# mbot_node.net
KiCad netlist of a schematic drawn in EasyEDA Pro
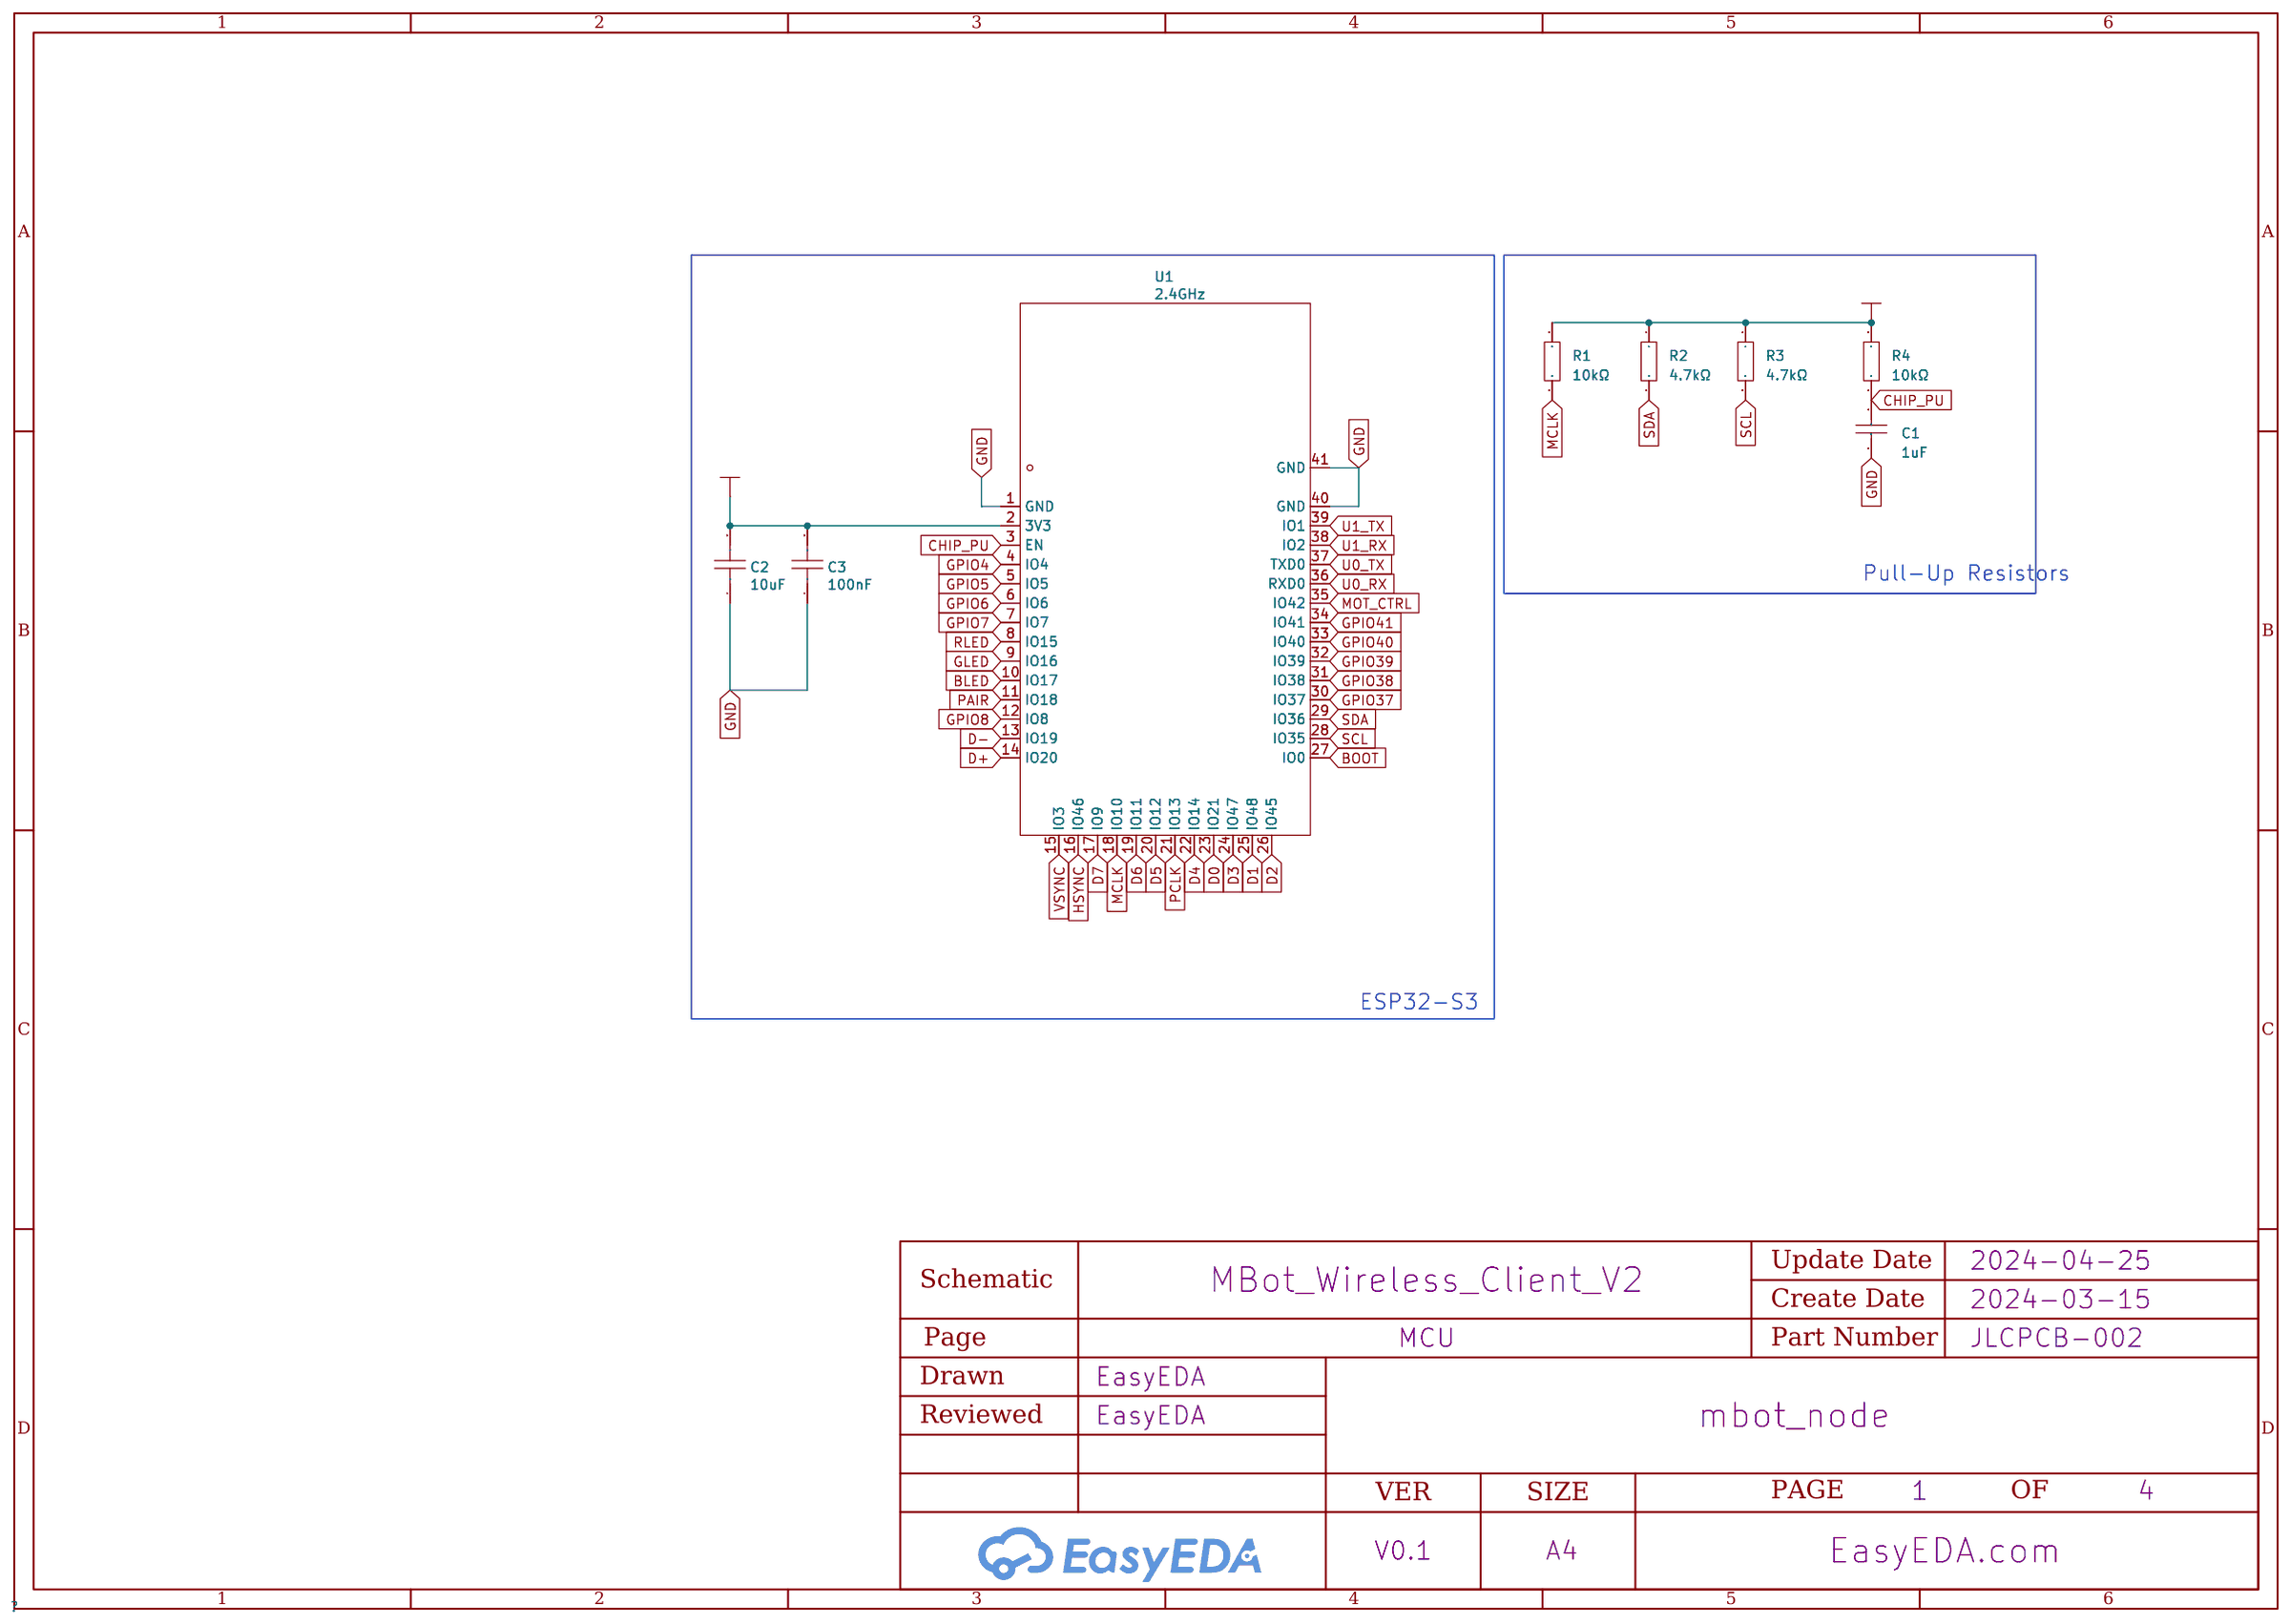
[diagram p0: MCU]
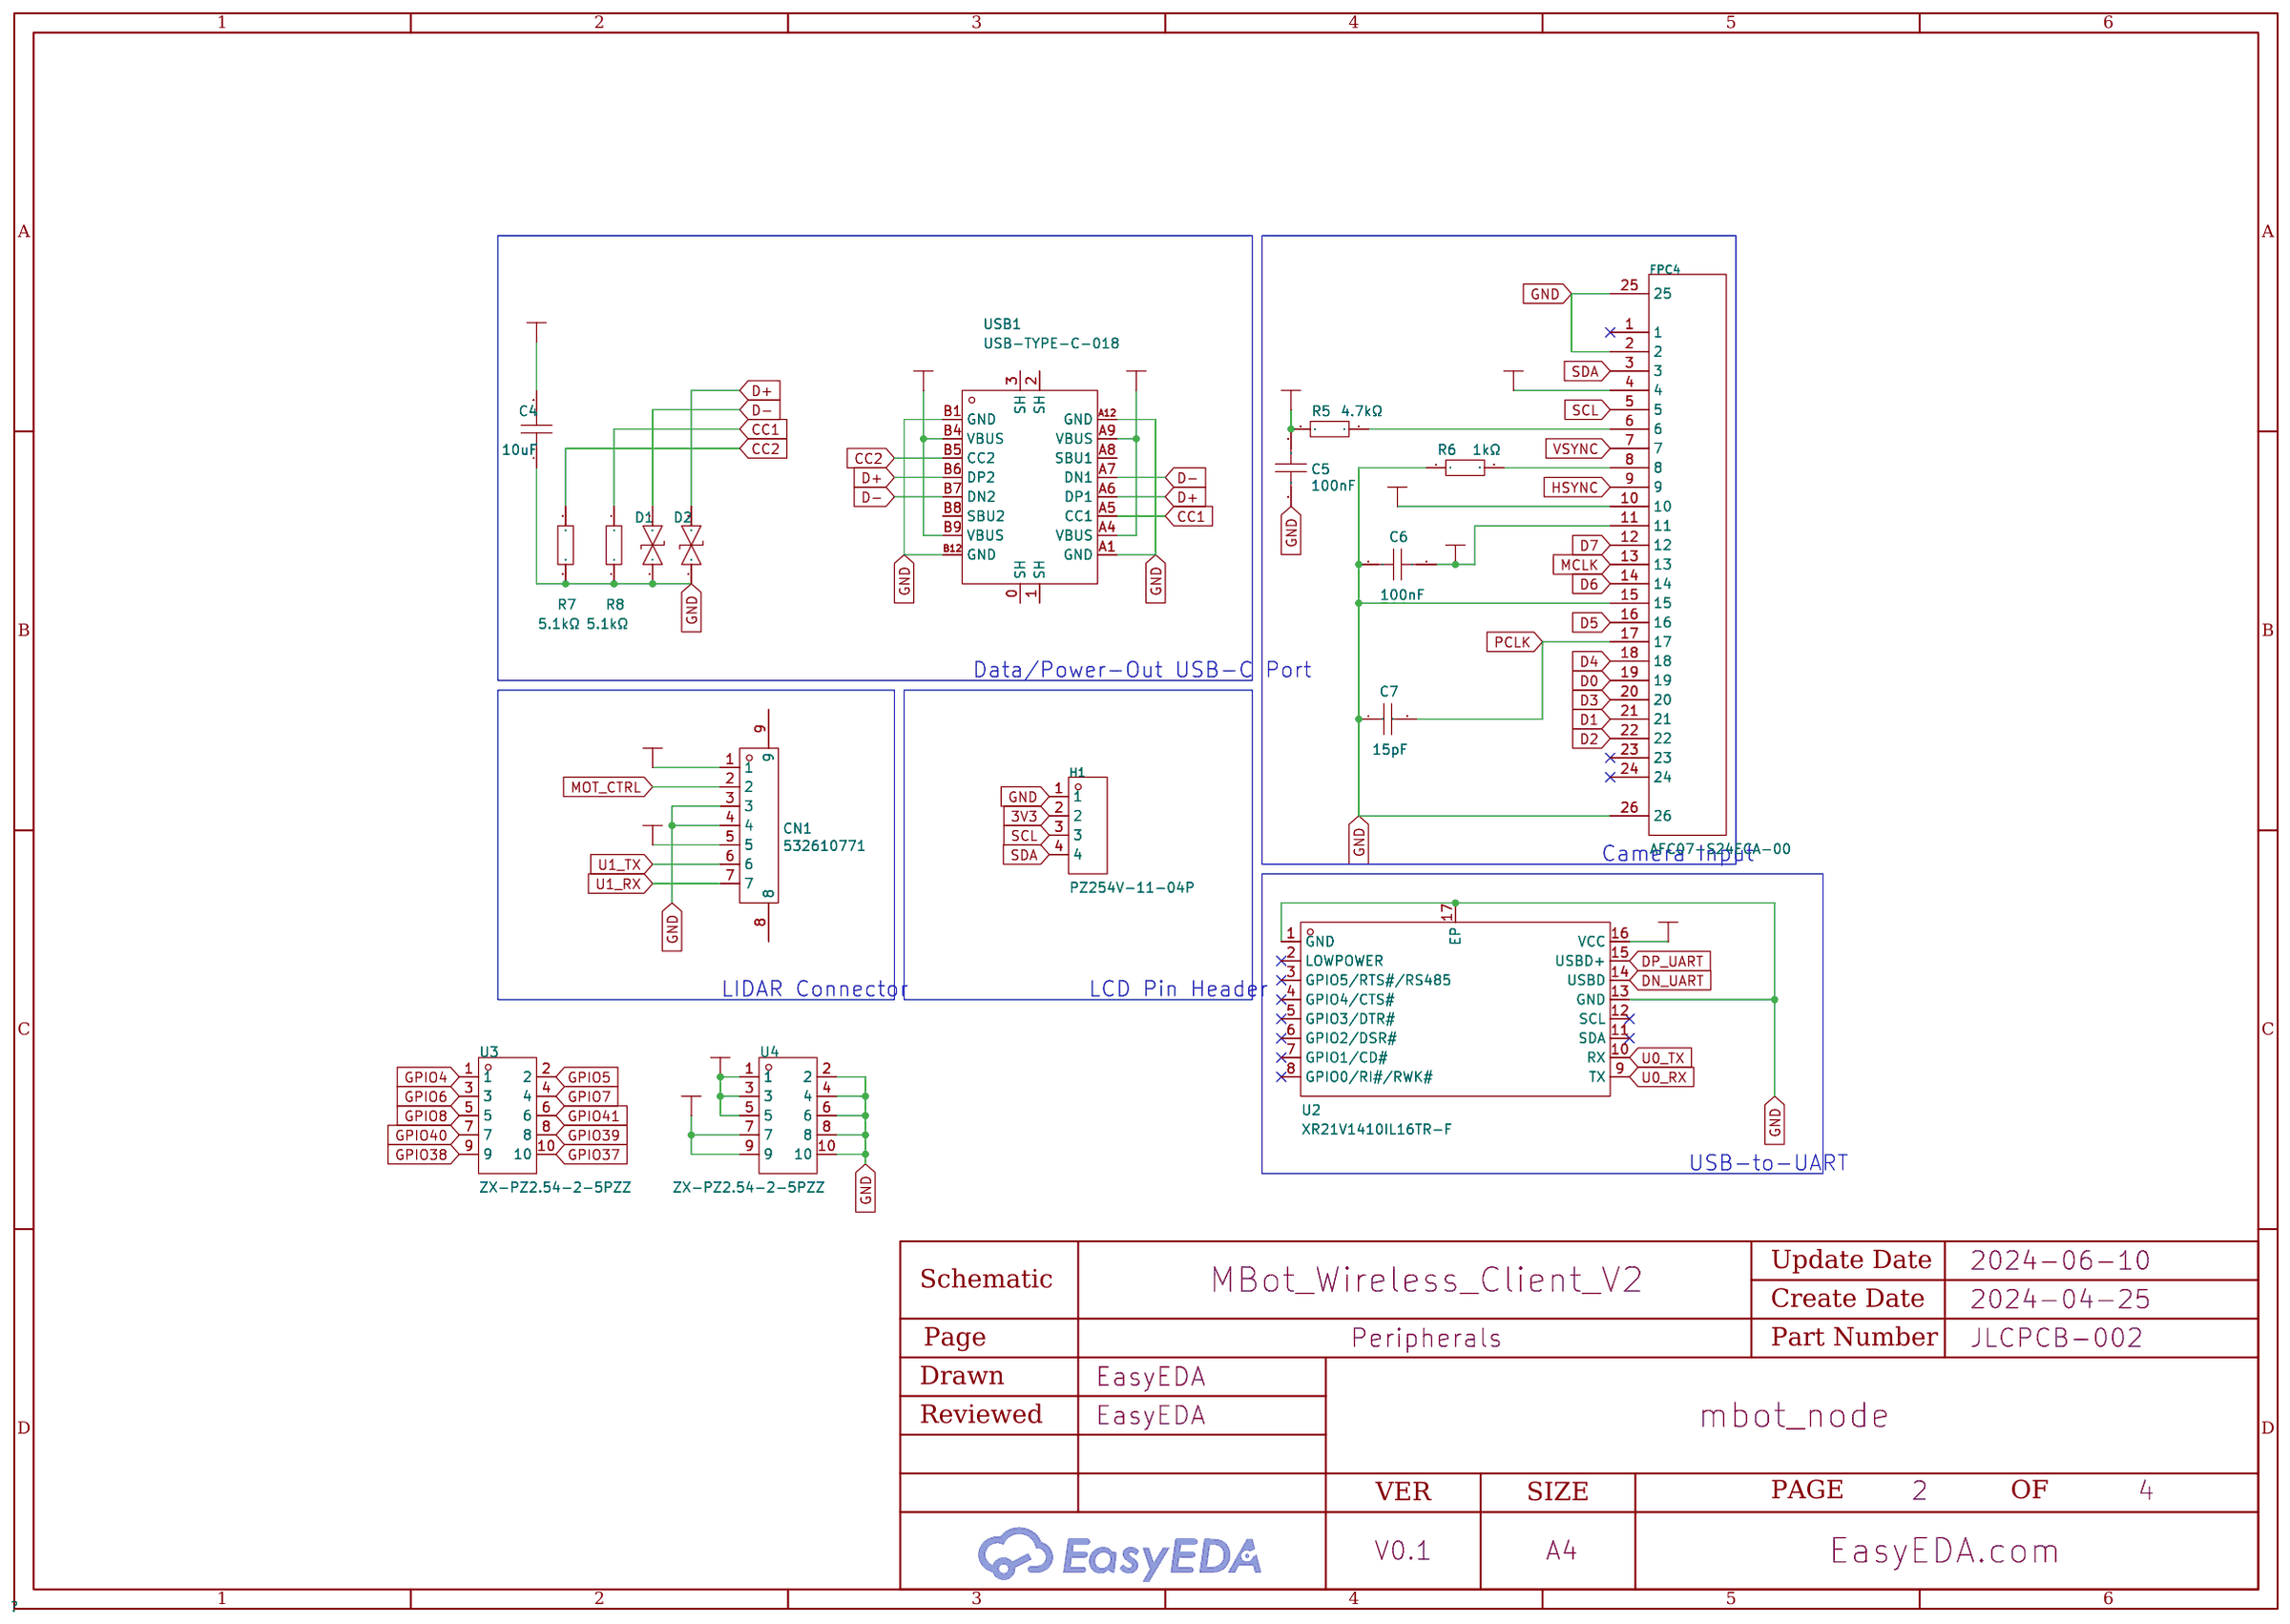
[diagram p1: Peripherals]
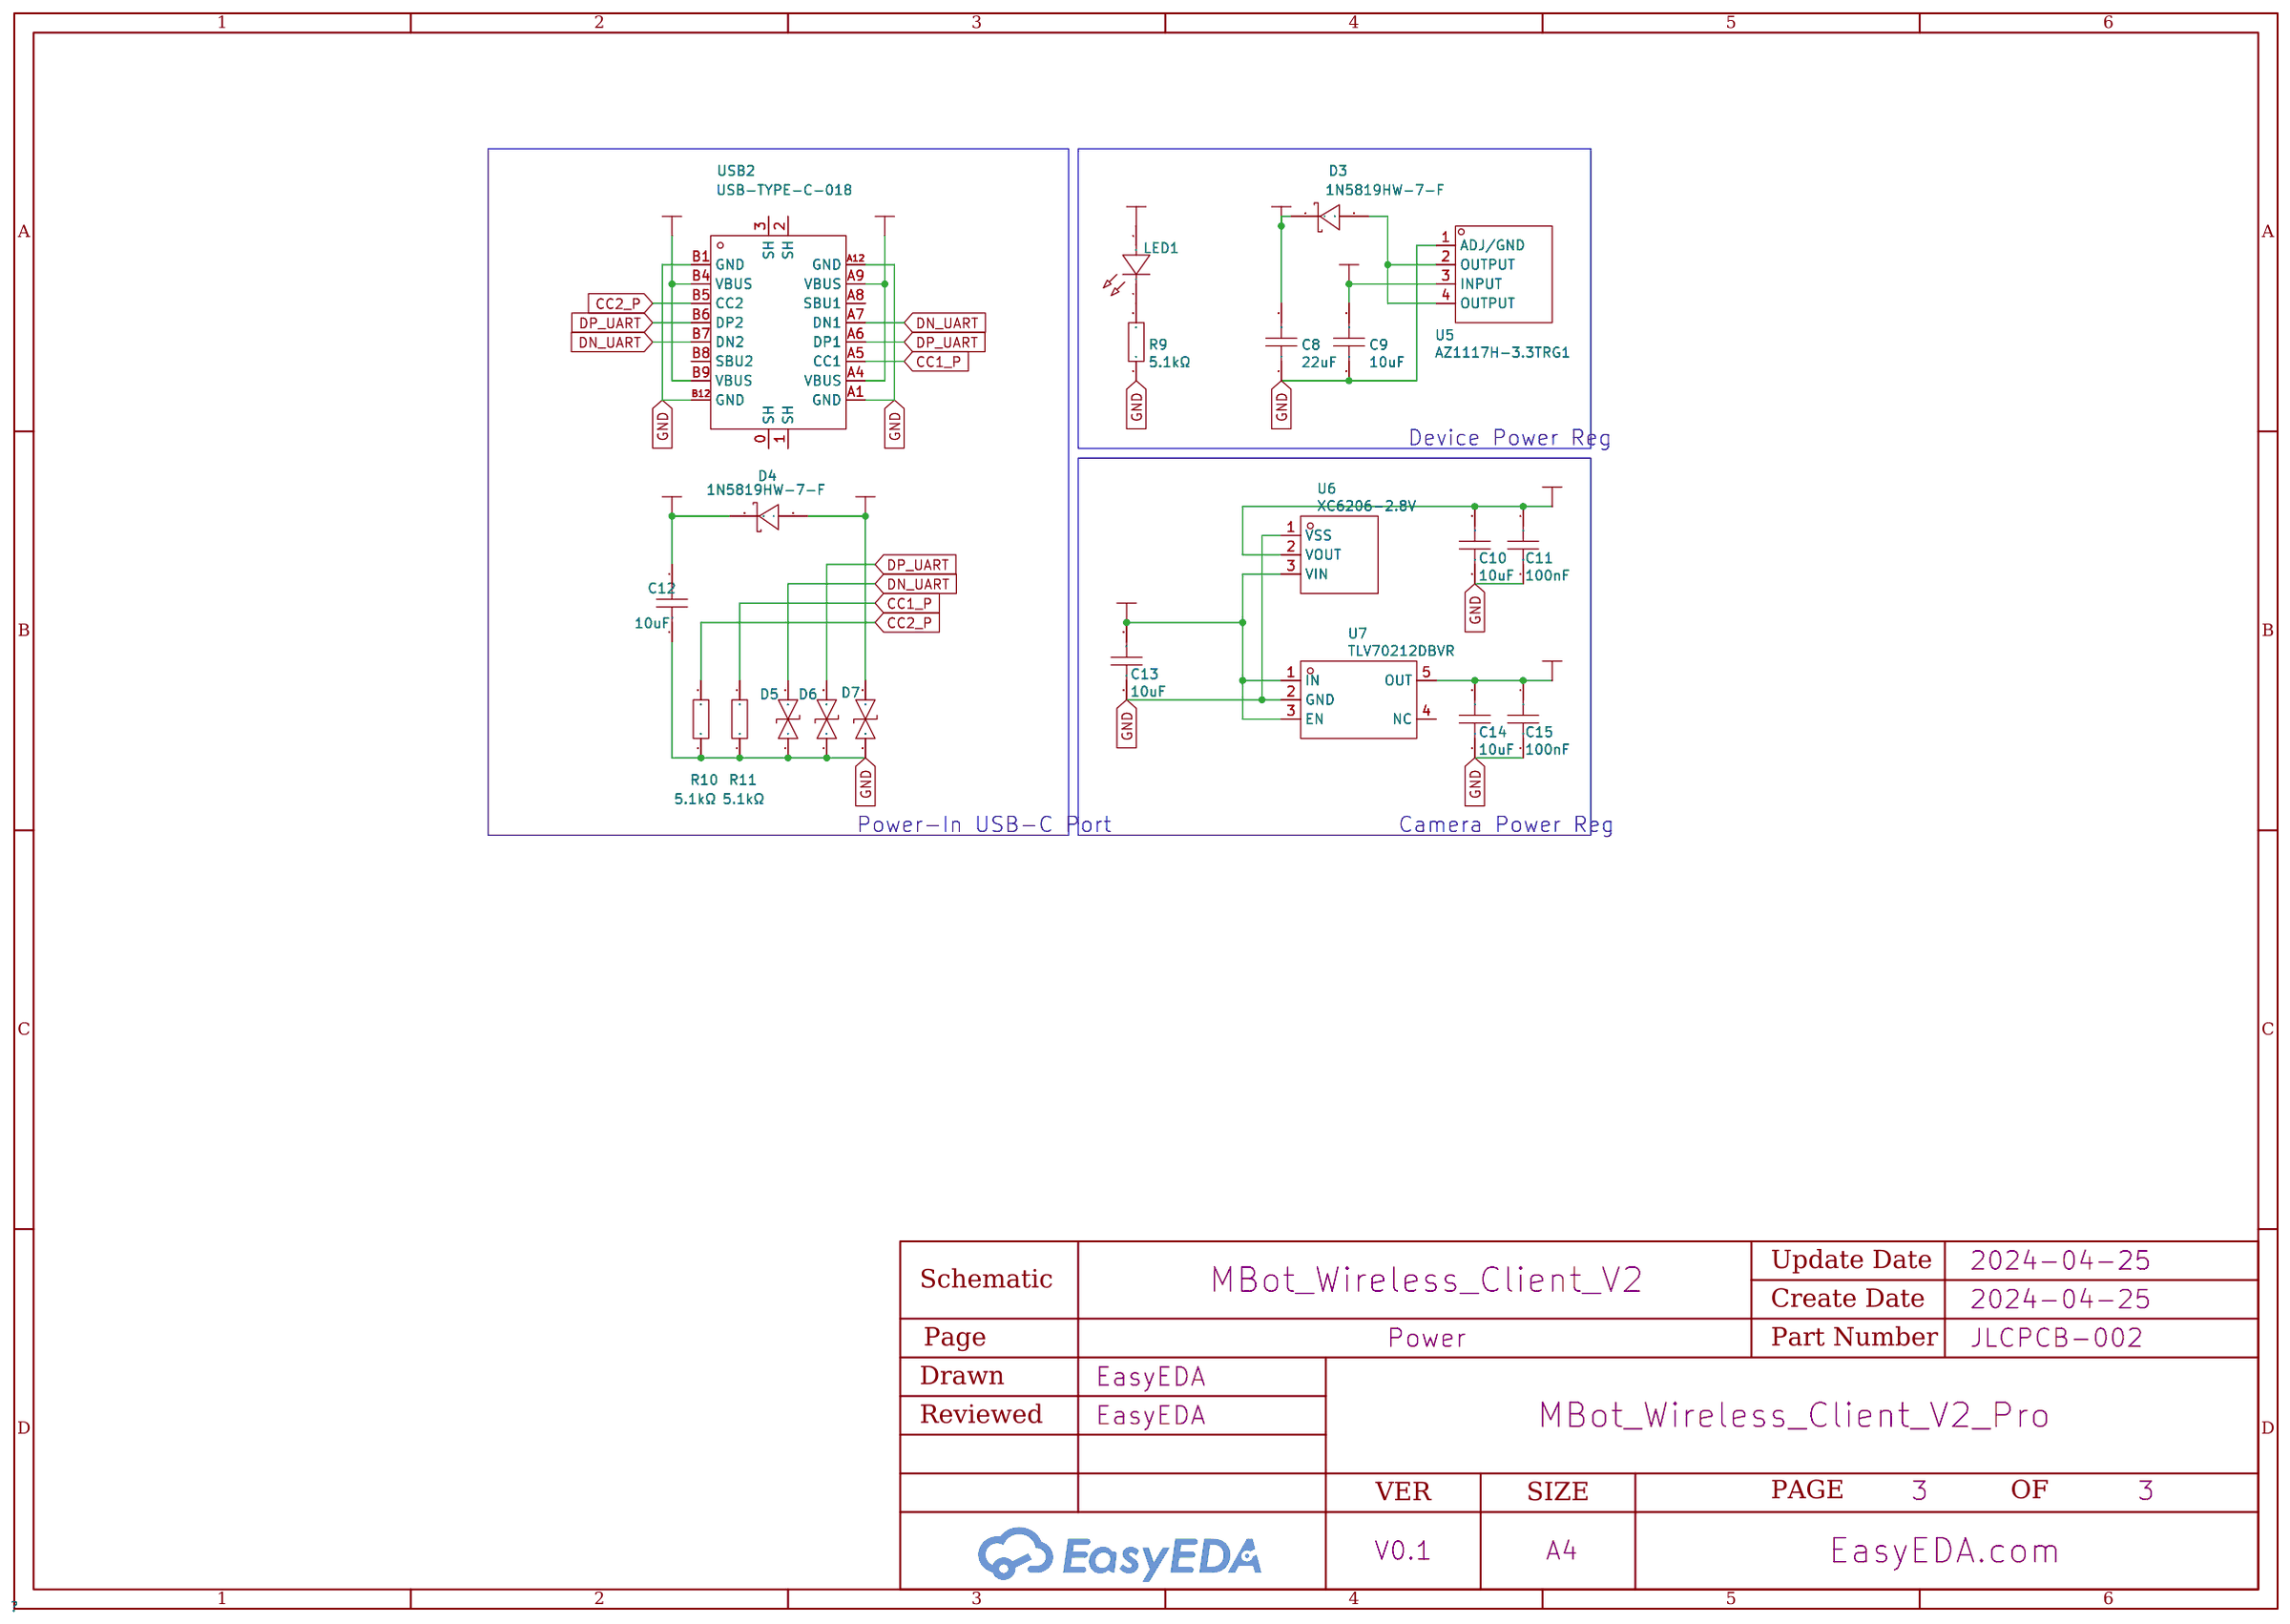
[diagram p2: Power]
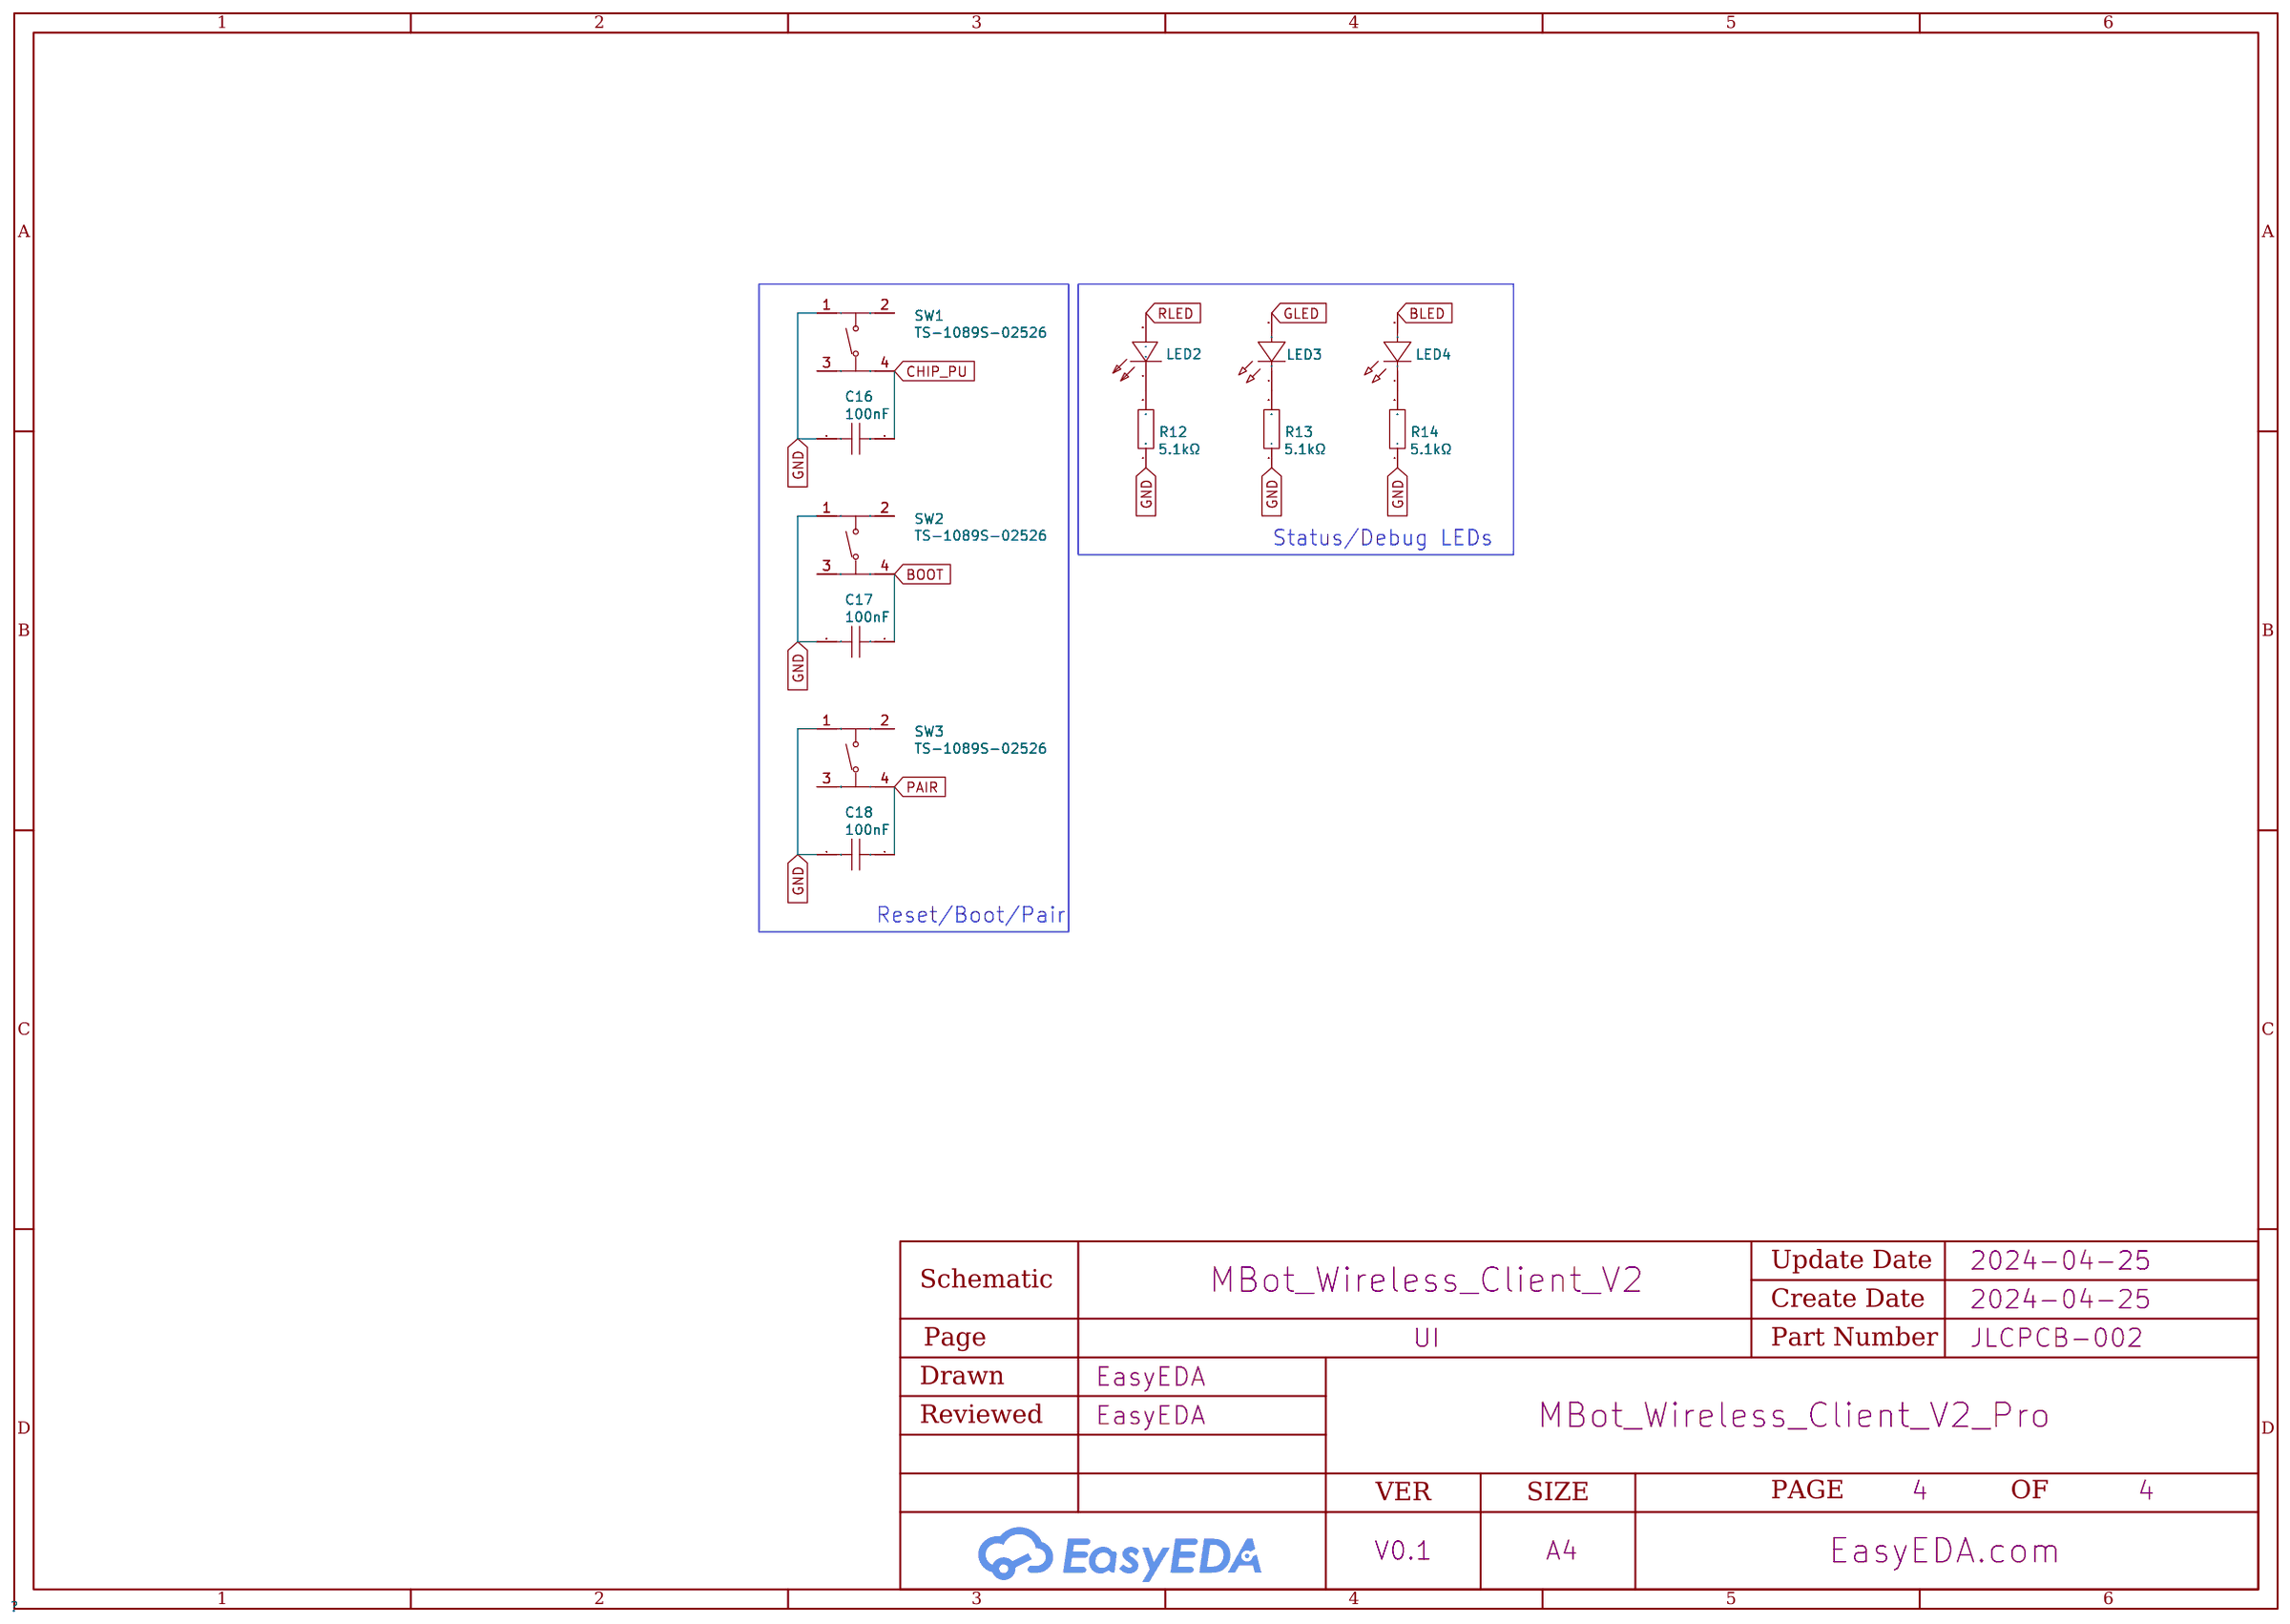
[diagram p3: UI]

(export (version "E")
  (design (tool "Eeschema 10.0.6"))
  (components
    (comp (ref "C1")
      (value "1uF")
      (footprint "easyedapro:C0603")
      (fields
        (field (name "Manufacturer Part") "CL10A105KO8NNNC")
        (field (name "Manufacturer") "SAMSUNG(三星)")
      )
      (libsource (lib "easyedapro") (part "CL10A105KO8NNNC"))
    )
    (comp (ref "C2")
      (value "10uF")
      (footprint "easyedapro:footprint_9d5d")
      (fields
        (field (name "Manufacturer Part") "CL10A106KP8NNNC")
        (field (name "Manufacturer") "SAMSUNG(三星)")
      )
      (libsource (lib "easyedapro") (part "10uF"))
    )
    (comp (ref "C3")
      (value "100nF")
      (footprint "easyedapro:footprint_9d5d")
      (fields
        (field (name "Manufacturer Part") "CC0603KRX7R9BB104")
        (field (name "Manufacturer") "YAGEO(国巨)")
      )
      (libsource (lib "easyedapro") (part "100nF"))
    )
    (comp (ref "R1")
      (value "10kΩ")
      (footprint "easyedapro:footprint_0f13")
      (fields
        (field (name "Manufacturer Part") "0603WAF1002T5E")
        (field (name "Manufacturer") "UNI-ROYAL(厚声)")
      )
      (libsource (lib "easyedapro") (part "10kΩ"))
    )
    (comp (ref "R2")
      (value "4.7kΩ")
      (footprint "easyedapro:footprint_0f13")
      (fields
        (field (name "Manufacturer Part") "0603WAF4701T5E")
        (field (name "Manufacturer") "UNI-ROYAL(厚声)")
      )
      (libsource (lib "easyedapro") (part "4.7kΩ"))
    )
    (comp (ref "R3")
      (value "4.7kΩ")
      (footprint "easyedapro:footprint_0f13")
      (fields
        (field (name "Manufacturer Part") "0603WAF4701T5E")
        (field (name "Manufacturer") "UNI-ROYAL(厚声)")
      )
      (libsource (lib "easyedapro") (part "4.7kΩ"))
    )
    (comp (ref "R4")
      (value "10kΩ")
      (footprint "easyedapro:footprint_0f13")
      (fields
        (field (name "Manufacturer Part") "0603WAF1002T5E")
        (field (name "Manufacturer") "UNI-ROYAL(厚声)")
      )
      (libsource (lib "easyedapro") (part "10kΩ"))
    )
    (comp (ref "U1")
      (value "2.4GHz")
      (footprint "easyedapro:footprint_0d45")
      (description "Core Processor:ESP32-S3芯片 Support Interface:I2C；GPIO；SPI；PWM；ADC；UART；USB；I2S Frequency:2.4GHz")
      (fields
        (field (name "Manufacturer Part") "ESP32-S3-WROOM-1-N8R2")
        (field (name "Manufacturer") "ESPRESSIF(乐鑫)")
      )
      (libsource (lib "easyedapro") (part "ESP32-S3-WROOM-1(N8R2)"))
    )
    (comp (ref "C4")
      (value "10uF")
      (footprint "easyedapro:footprint_9d5d")
      (fields
        (field (name "Manufacturer Part") "CL10A106KP8NNNC")
        (field (name "Manufacturer") "SAMSUNG(三星)")
      )
      (libsource (lib "easyedapro") (part "10uF"))
    )
    (comp (ref "C5")
      (value "100nF")
      (footprint "easyedapro:footprint_6050")
      (fields
        (field (name "Manufacturer Part") "CC0603KRX7R9BB104")
        (field (name "Manufacturer") "YAGEO(国巨)")
      )
      (libsource (lib "easyedapro") (part "0.1uF"))
    )
    (comp (ref "C6")
      (value "100nF")
      (footprint "easyedapro:footprint_6050")
      (fields
        (field (name "Manufacturer Part") "CC0603KRX7R9BB104")
        (field (name "Manufacturer") "YAGEO(国巨)")
      )
      (libsource (lib "easyedapro") (part "0.1uF"))
    )
    (comp (ref "C7")
      (value "15pF")
      (footprint "easyedapro:footprint_6050")
      (fields
        (field (name "Manufacturer Part") "CL10C150JB8NNNC")
        (field (name "Manufacturer") "SAMSUNG(三星)")
      )
      (libsource (lib "easyedapro") (part "15pF"))
    )
    (comp (ref "CN1")
      (value "532610771")
      (footprint "easyedapro:footprint_9fb3")
      (fields (field (name "Manufacturer") "MOLEX"))
      (libsource (lib "easyedapro") (part "532610771"))
    )
    (comp (ref "D1")
      (value "LESD5D5.0CT1G")
      (footprint "easyedapro:footprint_6954")
      (fields (field (name "Manufacturer") "LRC(乐山无线电)"))
      (libsource (lib "easyedapro") (part "LESD5D5.0CT1G"))
    )
    (comp (ref "D2")
      (value "LESD5D5.0CT1G")
      (footprint "easyedapro:footprint_6954")
      (fields (field (name "Manufacturer") "LRC(乐山无线电)"))
      (libsource (lib "easyedapro") (part "LESD5D5.0CT1G"))
    )
    (comp (ref "FPC4")
      (value "AFC07-S24ECA-00")
      (footprint "easyedapro:FPC-SMD_AFC07-S24ECA-00")
      (fields (field (name "Manufacturer") "JS(钜硕电子)"))
      (libsource (lib "easyedapro") (part "AFC07-S24ECA-00"))
    )
    (comp (ref "H1")
      (value "PZ254V-11-04P")
      (footprint "easyedapro:HDR-TH_4P-P2.54-V-M")
      (fields (field (name "Manufacturer") "XFCN(兴飞)"))
      (libsource (lib "easyedapro") (part "PZ254V-11-04P_C2691448"))
    )
    (comp (ref "R5")
      (value "4.7kΩ")
      (footprint "easyedapro:footprint_0f13")
      (fields
        (field (name "Manufacturer Part") "0603WAF4701T5E")
        (field (name "Manufacturer") "UNI-ROYAL(厚声)")
      )
      (libsource (lib "easyedapro") (part "4.7kΩ"))
    )
    (comp (ref "R6")
      (value "1kΩ")
      (footprint "easyedapro:footprint_03c1")
      (fields
        (field (name "Manufacturer Part") "0603WAF1001T5E")
        (field (name "Manufacturer") "UNI-ROYAL(厚声)")
      )
      (libsource (lib "easyedapro") (part "1kΩ"))
    )
    (comp (ref "R7")
      (value "5.1kΩ")
      (footprint "easyedapro:footprint_03c1")
      (fields
        (field (name "Manufacturer Part") "0603WAF5101T5E")
        (field (name "Manufacturer") "UNI-ROYAL(厚声)")
      )
      (libsource (lib "easyedapro") (part "5.1kΩ"))
    )
    (comp (ref "R8")
      (value "5.1kΩ")
      (footprint "easyedapro:footprint_03c1")
      (fields
        (field (name "Manufacturer Part") "0603WAF5101T5E")
        (field (name "Manufacturer") "UNI-ROYAL(厚声)")
      )
      (libsource (lib "easyedapro") (part "5.1kΩ"))
    )
    (comp (ref "U2")
      (value "XR21V1410IL16TR-F")
      (footprint "easyedapro:QFN-16_L3.0-W3.0-P0.50-BL-EP1.7")
      (fields (field (name "Manufacturer") "MaxLinear(迈凌)"))
      (libsource (lib "easyedapro") (part "XR21V1410IL16TR-F"))
    )
    (comp (ref "U3")
      (value "ZX-PZ2.54-2-5PZZ")
      (footprint "easyedapro:HDR-TH_10P-P2.54-V-M-R2-C5-S2.54")
      (fields (field (name "Manufacturer") "Megastar(兆星)"))
      (libsource (lib "easyedapro") (part "ZX-PZ2.54-2-5PZZ"))
    )
    (comp (ref "U4")
      (value "ZX-PZ2.54-2-5PZZ")
      (footprint "easyedapro:HDR-TH_10P-P2.54-V-M-R2-C5-S2.54")
      (fields (field (name "Manufacturer") "Megastar(兆星)"))
      (libsource (lib "easyedapro") (part "ZX-PZ2.54-2-5PZZ"))
    )
    (comp (ref "USB1")
      (value "USB-TYPE-C-018")
      (footprint "easyedapro:footprint_b0de")
      (fields (field (name "Manufacturer") "DEALON(德艺隆)"))
      (libsource (lib "easyedapro") (part "USB-TYPE-C-018"))
    )
    (comp (ref "C8")
      (value "22uF")
      (footprint "easyedapro:footprint_9d5d")
      (fields
        (field (name "Manufacturer Part") "CL10A226MQ8NRNC")
        (field (name "Manufacturer") "SAMSUNG(三星)")
      )
      (libsource (lib "easyedapro") (part "22uF"))
    )
    (comp (ref "C9")
      (value "10uF")
      (footprint "easyedapro:footprint_9d5d")
      (fields
        (field (name "Manufacturer Part") "CL10A106KP8NNNC")
        (field (name "Manufacturer") "SAMSUNG(三星)")
      )
      (libsource (lib "easyedapro") (part "10uF"))
    )
    (comp (ref "C10")
      (value "10uF")
      (footprint "easyedapro:footprint_9d5d")
      (fields
        (field (name "Manufacturer Part") "CL10A106KP8NNNC")
        (field (name "Manufacturer") "SAMSUNG(三星)")
      )
      (libsource (lib "easyedapro") (part "10uF"))
    )
    (comp (ref "C11")
      (value "100nF")
      (footprint "easyedapro:footprint_6050")
      (fields
        (field (name "Manufacturer Part") "CC0603KRX7R9BB104")
        (field (name "Manufacturer") "YAGEO(国巨)")
      )
      (libsource (lib "easyedapro") (part "0.1uF"))
    )
    (comp (ref "C12")
      (value "10uF")
      (footprint "easyedapro:footprint_9d5d")
      (fields
        (field (name "Manufacturer Part") "CL10A106KP8NNNC")
        (field (name "Manufacturer") "SAMSUNG(三星)")
      )
      (libsource (lib "easyedapro") (part "10uF"))
    )
    (comp (ref "C13")
      (value "10uF")
      (footprint "easyedapro:footprint_9d5d")
      (fields
        (field (name "Manufacturer Part") "CL10A106KP8NNNC")
        (field (name "Manufacturer") "SAMSUNG(三星)")
      )
      (libsource (lib "easyedapro") (part "10uF"))
    )
    (comp (ref "C14")
      (value "10uF")
      (footprint "easyedapro:footprint_9d5d")
      (fields
        (field (name "Manufacturer Part") "CL10A106KP8NNNC")
        (field (name "Manufacturer") "SAMSUNG(三星)")
      )
      (libsource (lib "easyedapro") (part "10uF"))
    )
    (comp (ref "C15")
      (value "100nF")
      (footprint "easyedapro:footprint_6050")
      (fields
        (field (name "Manufacturer Part") "CC0603KRX7R9BB104")
        (field (name "Manufacturer") "YAGEO(国巨)")
      )
      (libsource (lib "easyedapro") (part "0.1uF"))
    )
    (comp (ref "D3")
      (value "1N5819HW-7-F")
      (footprint "easyedapro:footprint_ca4d")
      (fields (field (name "Manufacturer") "DIODES(美台)"))
      (libsource (lib "easyedapro") (part "1N5819HW-7-F"))
    )
    (comp (ref "D4")
      (value "1N5819HW-7-F")
      (footprint "easyedapro:footprint_ca4d")
      (fields (field (name "Manufacturer") "DIODES(美台)"))
      (libsource (lib "easyedapro") (part "1N5819HW-7-F"))
    )
    (comp (ref "D5")
      (value "LESD5D5.0CT1G")
      (footprint "easyedapro:footprint_6954")
      (fields (field (name "Manufacturer") "LRC(乐山无线电)"))
      (libsource (lib "easyedapro") (part "LESD5D5.0CT1G"))
    )
    (comp (ref "D6")
      (value "LESD5D5.0CT1G")
      (footprint "easyedapro:footprint_6954")
      (fields (field (name "Manufacturer") "LRC(乐山无线电)"))
      (libsource (lib "easyedapro") (part "LESD5D5.0CT1G"))
    )
    (comp (ref "D7")
      (value "LESD5D5.0CT1G")
      (footprint "easyedapro:footprint_6954")
      (fields (field (name "Manufacturer") "LRC(乐山无线电)"))
      (libsource (lib "easyedapro") (part "LESD5D5.0CT1G"))
    )
    (comp (ref "LED1")
      (value "XL-1608UGC-04")
      (footprint "easyedapro:footprint_47f4")
      (fields (field (name "Manufacturer") "XINGLIGHT(成兴光)"))
      (libsource (lib "easyedapro") (part "XL-1608UGC-04"))
    )
    (comp (ref "R9")
      (value "5.1kΩ")
      (footprint "easyedapro:footprint_03c1")
      (fields
        (field (name "Manufacturer Part") "0603WAF5101T5E")
        (field (name "Manufacturer") "UNI-ROYAL(厚声)")
      )
      (libsource (lib "easyedapro") (part "5.1kΩ"))
    )
    (comp (ref "R10")
      (value "5.1kΩ")
      (footprint "easyedapro:footprint_03c1")
      (fields
        (field (name "Manufacturer Part") "0603WAF5101T5E")
        (field (name "Manufacturer") "UNI-ROYAL(厚声)")
      )
      (libsource (lib "easyedapro") (part "5.1kΩ"))
    )
    (comp (ref "R11")
      (value "5.1kΩ")
      (footprint "easyedapro:footprint_03c1")
      (fields
        (field (name "Manufacturer Part") "0603WAF5101T5E")
        (field (name "Manufacturer") "UNI-ROYAL(厚声)")
      )
      (libsource (lib "easyedapro") (part "5.1kΩ"))
    )
    (comp (ref "U5")
      (value "AZ1117H-3.3TRG1")
      (footprint "easyedapro:footprint_9a46")
      (fields (field (name "Manufacturer") "DIODES(美台)"))
      (libsource (lib "easyedapro") (part "AZ1117H-3.3TRG1"))
    )
    (comp (ref "U6")
      (value "XC6206-2.8V")
      (footprint "easyedapro:footprint_17ce")
      (fields (field (name "Manufacturer") "YONGYUTAI(永裕泰)"))
      (libsource (lib "easyedapro") (part "XC6206-2.8V"))
    )
    (comp (ref "U7")
      (value "TLV70212DBVR")
      (footprint "easyedapro:footprint_e85f")
      (fields (field (name "Manufacturer") "TI(德州仪器)"))
      (libsource (lib "easyedapro") (part "TLV70212DBVR"))
    )
    (comp (ref "USB2")
      (value "USB-TYPE-C-018")
      (footprint "easyedapro:footprint_b0de")
      (fields (field (name "Manufacturer") "DEALON(德艺隆)"))
      (libsource (lib "easyedapro") (part "USB-TYPE-C-018"))
    )
    (comp (ref "C16")
      (value "100nF")
      (footprint "easyedapro:footprint_6050")
      (fields
        (field (name "Manufacturer Part") "CC0603KRX7R9BB104")
        (field (name "Manufacturer") "YAGEO(国巨)")
      )
      (libsource (lib "easyedapro") (part "0.1uF"))
    )
    (comp (ref "C17")
      (value "100nF")
      (footprint "easyedapro:footprint_6050")
      (fields
        (field (name "Manufacturer Part") "CC0603KRX7R9BB104")
        (field (name "Manufacturer") "YAGEO(国巨)")
      )
      (libsource (lib "easyedapro") (part "0.1uF"))
    )
    (comp (ref "C18")
      (value "100nF")
      (footprint "easyedapro:footprint_6050")
      (fields
        (field (name "Manufacturer Part") "CC0603KRX7R9BB104")
        (field (name "Manufacturer") "YAGEO(国巨)")
      )
      (libsource (lib "easyedapro") (part "0.1uF"))
    )
    (comp (ref "LED2")
      (value "KT-0603R")
      (footprint "easyedapro:footprint_bd33")
      (fields (field (name "Manufacturer") "KENTO"))
      (libsource (lib "easyedapro") (part "KT-0603R"))
    )
    (comp (ref "LED3")
      (value "XL-1608UGC-04")
      (footprint "easyedapro:footprint_47f4")
      (fields (field (name "Manufacturer") "XINGLIGHT(成兴光)"))
      (libsource (lib "easyedapro") (part "XL-1608UGC-04"))
    )
    (comp (ref "LED4")
      (value "XL-1608UBC-04")
      (footprint "easyedapro:footprint_bd86")
      (fields (field (name "Manufacturer") "XINGLIGHT(成兴光)"))
      (libsource (lib "easyedapro") (part "XL-1608UBC-04"))
    )
    (comp (ref "R12")
      (value "5.1kΩ")
      (footprint "easyedapro:footprint_03c1")
      (fields
        (field (name "Manufacturer Part") "0603WAF5101T5E")
        (field (name "Manufacturer") "UNI-ROYAL(厚声)")
      )
      (libsource (lib "easyedapro") (part "5.1kΩ"))
    )
    (comp (ref "R13")
      (value "5.1kΩ")
      (footprint "easyedapro:footprint_03c1")
      (fields
        (field (name "Manufacturer Part") "0603WAF5101T5E")
        (field (name "Manufacturer") "UNI-ROYAL(厚声)")
      )
      (libsource (lib "easyedapro") (part "5.1kΩ"))
    )
    (comp (ref "R14")
      (value "5.1kΩ")
      (footprint "easyedapro:footprint_03c1")
      (fields
        (field (name "Manufacturer Part") "0603WAF5101T5E")
        (field (name "Manufacturer") "UNI-ROYAL(厚声)")
      )
      (libsource (lib "easyedapro") (part "5.1kΩ"))
    )
    (comp (ref "SW1")
      (value "TS-1089S-02526")
      (footprint "easyedapro:footprint_8499")
      (fields (field (name "Manufacturer") "XUNPU(讯普)"))
      (libsource (lib "easyedapro") (part "TS-1089S-02526"))
    )
    (comp (ref "SW2")
      (value "TS-1089S-02526")
      (footprint "easyedapro:footprint_8499")
      (fields (field (name "Manufacturer") "XUNPU(讯普)"))
      (libsource (lib "easyedapro") (part "TS-1089S-02526"))
    )
    (comp (ref "SW3")
      (value "TS-1089S-02526")
      (footprint "easyedapro:footprint_8499")
      (fields (field (name "Manufacturer") "XUNPU(讯普)"))
      (libsource (lib "easyedapro") (part "TS-1089S-02526"))
    )
  )
  (nets
    (net (code "1") (name "1V2") (class "Default")
      (node (ref "C14") (pin "2") (pinfunction "2_2") (pintype "unspecified"))
      (node (ref "C15") (pin "1") (pinfunction "1_1") (pintype "unspecified"))
      (node (ref "FPC4") (pin "10") (pinfunction "10_10") (pintype "input"))
      (node (ref "U7") (pin "5") (pinfunction "OUT_5") (pintype "unspecified"))
    )
    (net (code "2") (name "2V8") (class "Default")
      (node (ref "C10") (pin "2") (pinfunction "2_2") (pintype "unspecified"))
      (node (ref "C11") (pin "1") (pinfunction "1_1") (pintype "unspecified"))
      (node (ref "FPC4") (pin "4") (pinfunction "4_4") (pintype "input"))
      (node (ref "U6") (pin "2") (pinfunction "VOUT_2") (pintype "unspecified"))
    )
    (net (code "3") (name "3V3") (class "Default")
      (node (ref "C13") (pin "2") (pinfunction "2_2") (pintype "unspecified"))
      (node (ref "C2") (pin "2") (pinfunction "2_2") (pintype "unspecified"))
      (node (ref "C3") (pin "2") (pinfunction "2_2") (pintype "unspecified"))
      (node (ref "C5") (pin "1") (pinfunction "1_1") (pintype "unspecified"))
      (node (ref "C6") (pin "1") (pinfunction "1_1") (pintype "unspecified"))
      (node (ref "C8") (pin "2") (pinfunction "2_2") (pintype "unspecified"))
      (node (ref "D3") (pin "1") (pinfunction "K_1") (pintype "unspecified"))
      (node (ref "FPC4") (pin "11") (pinfunction "11_11") (pintype "input"))
      (node (ref "H1") (pin "2") (pinfunction "2_2") (pintype "input"))
      (node (ref "LED1") (pin "2") (pinfunction "A_2") (pintype "unspecified"))
      (node (ref "R1") (pin "2") (pinfunction "2_2") (pintype "input"))
      (node (ref "R2") (pin "1") (pinfunction "1_1") (pintype "input"))
      (node (ref "R3") (pin "1") (pinfunction "1_1") (pintype "input"))
      (node (ref "R4") (pin "2") (pinfunction "2_2") (pintype "input"))
      (node (ref "R5") (pin "2") (pinfunction "2_2") (pintype "input"))
      (node (ref "U1") (pin "2") (pinfunction "3V3_2") (pintype "unspecified"))
      (node (ref "U2") (pin "16") (pinfunction "VCC_16") (pintype "unspecified"))
      (node (ref "U4") (pin "1") (pinfunction "1_1") (pintype "unspecified"))
      (node (ref "U4") (pin "3") (pinfunction "3_3") (pintype "unspecified"))
      (node (ref "U4") (pin "5") (pinfunction "5_5") (pintype "unspecified"))
      (node (ref "U6") (pin "3") (pinfunction "VIN_3") (pintype "unspecified"))
      (node (ref "U7") (pin "1") (pinfunction "IN_1") (pintype "unspecified"))
      (node (ref "U7") (pin "3") (pinfunction "EN_3") (pintype "unspecified"))
    )
    (net (code "4") (name "5V") (class "Default")
      (node (ref "C12") (pin "2") (pinfunction "2_2") (pintype "unspecified"))
      (node (ref "C4") (pin "2") (pinfunction "2_2") (pintype "unspecified"))
      (node (ref "C9") (pin "2") (pinfunction "2_2") (pintype "unspecified"))
      (node (ref "CN1") (pin "1") (pinfunction "1_1") (pintype "unspecified"))
      (node (ref "CN1") (pin "5") (pinfunction "5_5") (pintype "unspecified"))
      (node (ref "D4") (pin "1") (pinfunction "K_1") (pintype "unspecified"))
      (node (ref "U4") (pin "7") (pinfunction "7_7") (pintype "unspecified"))
      (node (ref "U4") (pin "9") (pinfunction "9_9") (pintype "unspecified"))
      (node (ref "U5") (pin "3") (pinfunction "INPUT_3") (pintype "unspecified"))
      (node (ref "USB1") (pin "A4") (pinfunction "VBUS_A4") (pintype "unspecified"))
      (node (ref "USB1") (pin "A9") (pinfunction "VBUS_A9") (pintype "unspecified"))
      (node (ref "USB1") (pin "B4") (pinfunction "VBUS_B4") (pintype "unspecified"))
      (node (ref "USB1") (pin "B9") (pinfunction "VBUS_B9") (pintype "unspecified"))
    )
    (net (code "5") (name "BLED") (class "Default")
      (node (ref "LED4") (pin "2") (pinfunction "A_2") (pintype "unspecified"))
      (node (ref "U1") (pin "10") (pinfunction "IO17_10") (pintype "unspecified"))
    )
    (net (code "6") (name "BOOT") (class "Default")
      (node (ref "C17") (pin "1") (pinfunction "1_1") (pintype "unspecified"))
      (node (ref "SW2") (pin "4") (pinfunction "4_4") (pintype "unspecified"))
      (node (ref "U1") (pin "27") (pinfunction "IO0_27") (pintype "unspecified"))
    )
    (net (code "7") (name "CC1") (class "Default")
      (node (ref "R8") (pin "2") (pinfunction "2_2") (pintype "input"))
      (node (ref "USB1") (pin "A5") (pinfunction "CC1_A5") (pintype "unspecified"))
    )
    (net (code "8") (name "CC1_P") (class "Default")
      (node (ref "R11") (pin "2") (pinfunction "2_2") (pintype "input"))
      (node (ref "USB2") (pin "A5") (pinfunction "CC1_A5") (pintype "unspecified"))
    )
    (net (code "9") (name "CC2") (class "Default")
      (node (ref "R7") (pin "2") (pinfunction "2_2") (pintype "input"))
      (node (ref "USB1") (pin "B5") (pinfunction "CC2_B5") (pintype "unspecified"))
    )
    (net (code "10") (name "CC2_P") (class "Default")
      (node (ref "R10") (pin "2") (pinfunction "2_2") (pintype "input"))
      (node (ref "USB2") (pin "B5") (pinfunction "CC2_B5") (pintype "unspecified"))
    )
    (net (code "11") (name "CHIP_PU") (class "Default")
      (node (ref "C1") (pin "2") (pinfunction "2_2") (pintype "input"))
      (node (ref "C16") (pin "1") (pinfunction "1_1") (pintype "unspecified"))
      (node (ref "R4") (pin "1") (pinfunction "1_1") (pintype "input"))
      (node (ref "SW1") (pin "4") (pinfunction "4_4") (pintype "unspecified"))
      (node (ref "U1") (pin "3") (pinfunction "EN_3") (pintype "unspecified"))
    )
    (net (code "12") (name "D+") (class "Default")
      (node (ref "D2") (pin "2") (pinfunction "2_2") (pintype "unspecified"))
      (node (ref "U1") (pin "14") (pinfunction "IO20_14") (pintype "unspecified"))
      (node (ref "USB1") (pin "A6") (pinfunction "DP1_A6") (pintype "unspecified"))
      (node (ref "USB1") (pin "B6") (pinfunction "DP2_B6") (pintype "unspecified"))
    )
    (net (code "13") (name "D-") (class "Default")
      (node (ref "D1") (pin "2") (pinfunction "2_2") (pintype "unspecified"))
      (node (ref "U1") (pin "13") (pinfunction "IO19_13") (pintype "unspecified"))
      (node (ref "USB1") (pin "A7") (pinfunction "DN1_A7") (pintype "unspecified"))
      (node (ref "USB1") (pin "B7") (pinfunction "DN2_B7") (pintype "unspecified"))
    )
    (net (code "14") (name "D0") (class "Default")
      (node (ref "FPC4") (pin "19") (pinfunction "19_19") (pintype "input"))
      (node (ref "U1") (pin "23") (pinfunction "IO21_23") (pintype "unspecified"))
    )
    (net (code "15") (name "D1") (class "Default")
      (node (ref "FPC4") (pin "21") (pinfunction "21_21") (pintype "input"))
      (node (ref "U1") (pin "25") (pinfunction "IO48_25") (pintype "unspecified"))
    )
    (net (code "16") (name "D2") (class "Default")
      (node (ref "FPC4") (pin "22") (pinfunction "22_22") (pintype "input"))
      (node (ref "U1") (pin "26") (pinfunction "IO45_26") (pintype "unspecified"))
    )
    (net (code "17") (name "D3") (class "Default")
      (node (ref "FPC4") (pin "20") (pinfunction "20_20") (pintype "input"))
      (node (ref "U1") (pin "24") (pinfunction "IO47_24") (pintype "unspecified"))
    )
    (net (code "18") (name "D4") (class "Default")
      (node (ref "FPC4") (pin "18") (pinfunction "18_18") (pintype "input"))
      (node (ref "U1") (pin "22") (pinfunction "IO14_22") (pintype "unspecified"))
    )
    (net (code "19") (name "D5") (class "Default")
      (node (ref "FPC4") (pin "16") (pinfunction "16_16") (pintype "input"))
      (node (ref "U1") (pin "20") (pinfunction "IO12_20") (pintype "unspecified"))
    )
    (net (code "20") (name "D6") (class "Default")
      (node (ref "FPC4") (pin "14") (pinfunction "14_14") (pintype "input"))
      (node (ref "U1") (pin "19") (pinfunction "IO11_19") (pintype "unspecified"))
    )
    (net (code "21") (name "D7") (class "Default")
      (node (ref "FPC4") (pin "12") (pinfunction "12_12") (pintype "input"))
      (node (ref "U1") (pin "17") (pinfunction "IO9_17") (pintype "unspecified"))
    )
    (net (code "22") (name "DN_UART") (class "Default")
      (node (ref "D5") (pin "2") (pinfunction "2_2") (pintype "unspecified"))
      (node (ref "U2") (pin "14") (pinfunction "USBD_14") (pintype "unspecified"))
      (node (ref "USB2") (pin "A7") (pinfunction "DN1_A7") (pintype "unspecified"))
      (node (ref "USB2") (pin "B7") (pinfunction "DN2_B7") (pintype "unspecified"))
    )
    (net (code "23") (name "DP_UART") (class "Default")
      (node (ref "D6") (pin "2") (pinfunction "2_2") (pintype "unspecified"))
      (node (ref "U2") (pin "15") (pinfunction "USBD+_15") (pintype "unspecified"))
      (node (ref "USB2") (pin "A6") (pinfunction "DP1_A6") (pintype "unspecified"))
      (node (ref "USB2") (pin "B6") (pinfunction "DP2_B6") (pintype "unspecified"))
    )
    (net (code "24") (name "GLED") (class "Default")
      (node (ref "LED3") (pin "2") (pinfunction "A_2") (pintype "unspecified"))
      (node (ref "U1") (pin "9") (pinfunction "IO16_9") (pintype "unspecified"))
    )
    (net (code "25") (name "GND") (class "Default")
      (node (ref "C1") (pin "1") (pinfunction "1_1") (pintype "input"))
      (node (ref "C10") (pin "1") (pinfunction "1_1") (pintype "unspecified"))
      (node (ref "C11") (pin "2") (pinfunction "2_2") (pintype "unspecified"))
      (node (ref "C12") (pin "1") (pinfunction "1_1") (pintype "unspecified"))
      (node (ref "C13") (pin "1") (pinfunction "1_1") (pintype "unspecified"))
      (node (ref "C14") (pin "1") (pinfunction "1_1") (pintype "unspecified"))
      (node (ref "C15") (pin "2") (pinfunction "2_2") (pintype "unspecified"))
      (node (ref "C16") (pin "2") (pinfunction "2_2") (pintype "unspecified"))
      (node (ref "C17") (pin "2") (pinfunction "2_2") (pintype "unspecified"))
      (node (ref "C18") (pin "2") (pinfunction "2_2") (pintype "unspecified"))
      (node (ref "C2") (pin "1") (pinfunction "1_1") (pintype "unspecified"))
      (node (ref "C3") (pin "1") (pinfunction "1_1") (pintype "unspecified"))
      (node (ref "C4") (pin "1") (pinfunction "1_1") (pintype "unspecified"))
      (node (ref "C5") (pin "2") (pinfunction "2_2") (pintype "unspecified"))
      (node (ref "C6") (pin "2") (pinfunction "2_2") (pintype "unspecified"))
      (node (ref "C7") (pin "1") (pinfunction "1_1") (pintype "input"))
      (node (ref "C8") (pin "1") (pinfunction "1_1") (pintype "unspecified"))
      (node (ref "C9") (pin "1") (pinfunction "1_1") (pintype "unspecified"))
      (node (ref "CN1") (pin "3") (pinfunction "3_3") (pintype "unspecified"))
      (node (ref "CN1") (pin "4") (pinfunction "4_4") (pintype "unspecified"))
      (node (ref "D1") (pin "1") (pinfunction "1_1") (pintype "unspecified"))
      (node (ref "D2") (pin "1") (pinfunction "1_1") (pintype "unspecified"))
      (node (ref "D5") (pin "1") (pinfunction "1_1") (pintype "unspecified"))
      (node (ref "D6") (pin "1") (pinfunction "1_1") (pintype "unspecified"))
      (node (ref "D7") (pin "1") (pinfunction "1_1") (pintype "unspecified"))
      (node (ref "FPC4") (pin "15") (pinfunction "15_15") (pintype "input"))
      (node (ref "FPC4") (pin "2") (pinfunction "2_2") (pintype "input"))
      (node (ref "FPC4") (pin "25") (pinfunction "25_25") (pintype "input"))
      (node (ref "FPC4") (pin "26") (pinfunction "26_26") (pintype "input"))
      (node (ref "H1") (pin "1") (pinfunction "1_1") (pintype "input"))
      (node (ref "R10") (pin "1") (pinfunction "1_1") (pintype "input"))
      (node (ref "R11") (pin "1") (pinfunction "1_1") (pintype "input"))
      (node (ref "R12") (pin "1") (pinfunction "1_1") (pintype "input"))
      (node (ref "R13") (pin "1") (pinfunction "1_1") (pintype "input"))
      (node (ref "R14") (pin "1") (pinfunction "1_1") (pintype "input"))
      (node (ref "R6") (pin "1") (pinfunction "1_1") (pintype "input"))
      (node (ref "R7") (pin "1") (pinfunction "1_1") (pintype "input"))
      (node (ref "R8") (pin "1") (pinfunction "1_1") (pintype "input"))
      (node (ref "R9") (pin "1") (pinfunction "1_1") (pintype "input"))
      (node (ref "SW1") (pin "1") (pinfunction "1_1") (pintype "unspecified"))
      (node (ref "SW2") (pin "1") (pinfunction "1_1") (pintype "unspecified"))
      (node (ref "SW3") (pin "1") (pinfunction "1_1") (pintype "unspecified"))
      (node (ref "U1") (pin "1") (pinfunction "GND_1") (pintype "unspecified"))
      (node (ref "U1") (pin "40") (pinfunction "GND_40") (pintype "unspecified"))
      (node (ref "U1") (pin "41") (pinfunction "GND_41") (pintype "unspecified"))
      (node (ref "U2") (pin "1") (pinfunction "GND_1") (pintype "unspecified"))
      (node (ref "U2") (pin "13") (pinfunction "GND_13") (pintype "unspecified"))
      (node (ref "U2") (pin "17") (pinfunction "EP_17") (pintype "unspecified"))
      (node (ref "U4") (pin "10") (pinfunction "10_10") (pintype "unspecified"))
      (node (ref "U4") (pin "2") (pinfunction "2_2") (pintype "unspecified"))
      (node (ref "U4") (pin "4") (pinfunction "4_4") (pintype "unspecified"))
      (node (ref "U4") (pin "6") (pinfunction "6_6") (pintype "unspecified"))
      (node (ref "U4") (pin "8") (pinfunction "8_8") (pintype "unspecified"))
      (node (ref "U5") (pin "1") (pinfunction "ADJ/GND_1") (pintype "unspecified"))
      (node (ref "U6") (pin "1") (pinfunction "VSS_1") (pintype "unspecified"))
      (node (ref "U7") (pin "2") (pinfunction "GND_2") (pintype "unspecified"))
      (node (ref "USB1") (pin "A1") (pinfunction "GND_A1") (pintype "unspecified"))
      (node (ref "USB1") (pin "A12") (pinfunction "GND_A12") (pintype "unspecified"))
      (node (ref "USB1") (pin "B1") (pinfunction "GND_B1") (pintype "unspecified"))
      (node (ref "USB1") (pin "B12") (pinfunction "GND_B12") (pintype "unspecified"))
      (node (ref "USB2") (pin "A1") (pinfunction "GND_A1") (pintype "unspecified"))
      (node (ref "USB2") (pin "A12") (pinfunction "GND_A12") (pintype "unspecified"))
      (node (ref "USB2") (pin "B1") (pinfunction "GND_B1") (pintype "unspecified"))
      (node (ref "USB2") (pin "B12") (pinfunction "GND_B12") (pintype "unspecified"))
    )
    (net (code "26") (name "GPIO4") (class "Default")
      (node (ref "U1") (pin "4") (pinfunction "IO4_4") (pintype "unspecified"))
      (node (ref "U3") (pin "1") (pinfunction "1_1") (pintype "unspecified"))
    )
    (net (code "27") (name "GPIO5") (class "Default")
      (node (ref "U1") (pin "5") (pinfunction "IO5_5") (pintype "unspecified"))
      (node (ref "U3") (pin "2") (pinfunction "2_2") (pintype "unspecified"))
    )
    (net (code "28") (name "GPIO6") (class "Default")
      (node (ref "U1") (pin "6") (pinfunction "IO6_6") (pintype "unspecified"))
      (node (ref "U3") (pin "3") (pinfunction "3_3") (pintype "unspecified"))
    )
    (net (code "29") (name "GPIO7") (class "Default")
      (node (ref "U1") (pin "7") (pinfunction "IO7_7") (pintype "unspecified"))
      (node (ref "U3") (pin "4") (pinfunction "4_4") (pintype "unspecified"))
    )
    (net (code "30") (name "GPIO8") (class "Default")
      (node (ref "U1") (pin "12") (pinfunction "IO8_12") (pintype "unspecified"))
      (node (ref "U3") (pin "5") (pinfunction "5_5") (pintype "unspecified"))
    )
    (net (code "31") (name "GPIO37") (class "Default")
      (node (ref "U1") (pin "30") (pinfunction "IO37_30") (pintype "unspecified"))
      (node (ref "U3") (pin "10") (pinfunction "10_10") (pintype "unspecified"))
    )
    (net (code "32") (name "GPIO38") (class "Default")
      (node (ref "U1") (pin "31") (pinfunction "IO38_31") (pintype "unspecified"))
      (node (ref "U3") (pin "9") (pinfunction "9_9") (pintype "unspecified"))
    )
    (net (code "33") (name "GPIO39") (class "Default")
      (node (ref "U1") (pin "32") (pinfunction "IO39_32") (pintype "unspecified"))
      (node (ref "U3") (pin "8") (pinfunction "8_8") (pintype "unspecified"))
    )
    (net (code "34") (name "GPIO40") (class "Default")
      (node (ref "U1") (pin "33") (pinfunction "IO40_33") (pintype "unspecified"))
      (node (ref "U3") (pin "7") (pinfunction "7_7") (pintype "unspecified"))
    )
    (net (code "35") (name "GPIO41") (class "Default")
      (node (ref "U1") (pin "34") (pinfunction "IO41_34") (pintype "unspecified"))
      (node (ref "U3") (pin "6") (pinfunction "6_6") (pintype "unspecified"))
    )
    (net (code "36") (name "HSYNC") (class "Default")
      (node (ref "FPC4") (pin "9") (pinfunction "9_9") (pintype "input"))
      (node (ref "U1") (pin "16") (pinfunction "IO46_16") (pintype "unspecified"))
    )
    (net (code "37") (name "MCLK") (class "Default")
      (node (ref "FPC4") (pin "13") (pinfunction "13_13") (pintype "input"))
      (node (ref "R1") (pin "1") (pinfunction "1_1") (pintype "input"))
      (node (ref "U1") (pin "18") (pinfunction "IO10_18") (pintype "unspecified"))
    )
    (net (code "38") (name "MOT_CTRL") (class "Default")
      (node (ref "CN1") (pin "2") (pinfunction "2_2") (pintype "unspecified"))
      (node (ref "U1") (pin "35") (pinfunction "IO42_35") (pintype "unspecified"))
    )
    (net (code "39") (name "Net-(D3-A)") (class "Default")
      (node (ref "D3") (pin "2") (pinfunction "A_2") (pintype "unspecified"))
      (node (ref "U5") (pin "2") (pinfunction "OUTPUT_2") (pintype "unspecified"))
      (node (ref "U5") (pin "4") (pinfunction "OUTPUT_4") (pintype "unspecified"))
    )
    (net (code "40") (name "Net-(FPC4-Pad6)") (class "Default")
      (node (ref "FPC4") (pin "6") (pinfunction "6_6") (pintype "input"))
      (node (ref "R5") (pin "1") (pinfunction "1_1") (pintype "input"))
    )
    (net (code "41") (name "Net-(FPC4-Pad8)") (class "Default")
      (node (ref "FPC4") (pin "8") (pinfunction "8_8") (pintype "input"))
      (node (ref "R6") (pin "2") (pinfunction "2_2") (pintype "input"))
    )
    (net (code "42") (name "Net-(LED1-K)") (class "Default")
      (node (ref "LED1") (pin "1") (pinfunction "K_1") (pintype "unspecified"))
      (node (ref "R9") (pin "2") (pinfunction "2_2") (pintype "input"))
    )
    (net (code "43") (name "Net-(LED2-K)") (class "Default")
      (node (ref "LED2") (pin "1") (pinfunction "K_1") (pintype "unspecified"))
      (node (ref "R12") (pin "2") (pinfunction "2_2") (pintype "input"))
    )
    (net (code "44") (name "Net-(LED3-K)") (class "Default")
      (node (ref "LED3") (pin "1") (pinfunction "K_1") (pintype "unspecified"))
      (node (ref "R13") (pin "2") (pinfunction "2_2") (pintype "input"))
    )
    (net (code "45") (name "Net-(LED4-K)") (class "Default")
      (node (ref "LED4") (pin "1") (pinfunction "K_1") (pintype "unspecified"))
      (node (ref "R14") (pin "2") (pinfunction "2_2") (pintype "input"))
    )
    (net (code "46") (name "PAIR") (class "Default")
      (node (ref "C18") (pin "1") (pinfunction "1_1") (pintype "unspecified"))
      (node (ref "SW3") (pin "4") (pinfunction "4_4") (pintype "unspecified"))
      (node (ref "U1") (pin "11") (pinfunction "IO18_11") (pintype "unspecified"))
    )
    (net (code "47") (name "PCLK") (class "Default")
      (node (ref "C7") (pin "2") (pinfunction "2_2") (pintype "input"))
      (node (ref "FPC4") (pin "17") (pinfunction "17_17") (pintype "input"))
      (node (ref "U1") (pin "21") (pinfunction "IO13_21") (pintype "unspecified"))
    )
    (net (code "48") (name "RLED") (class "Default")
      (node (ref "LED2") (pin "2") (pinfunction "A_2") (pintype "unspecified"))
      (node (ref "U1") (pin "8") (pinfunction "IO15_8") (pintype "unspecified"))
    )
    (net (code "49") (name "SCL") (class "Default")
      (node (ref "FPC4") (pin "5") (pinfunction "5_5") (pintype "input"))
      (node (ref "H1") (pin "3") (pinfunction "3_3") (pintype "input"))
      (node (ref "R3") (pin "2") (pinfunction "2_2") (pintype "input"))
      (node (ref "U1") (pin "28") (pinfunction "IO35_28") (pintype "unspecified"))
    )
    (net (code "50") (name "SDA") (class "Default")
      (node (ref "FPC4") (pin "3") (pinfunction "3_3") (pintype "input"))
      (node (ref "H1") (pin "4") (pinfunction "4_4") (pintype "input"))
      (node (ref "R2") (pin "2") (pinfunction "2_2") (pintype "input"))
      (node (ref "U1") (pin "29") (pinfunction "IO36_29") (pintype "unspecified"))
    )
    (net (code "51") (name "U0_RX") (class "Default")
      (node (ref "U1") (pin "36") (pinfunction "RXD0_36") (pintype "unspecified"))
      (node (ref "U2") (pin "9") (pinfunction "TX_9") (pintype "unspecified"))
    )
    (net (code "52") (name "U0_TX") (class "Default")
      (node (ref "U1") (pin "37") (pinfunction "TXD0_37") (pintype "unspecified"))
      (node (ref "U2") (pin "10") (pinfunction "RX_10") (pintype "unspecified"))
    )
    (net (code "53") (name "U1_RX") (class "Default")
      (node (ref "CN1") (pin "7") (pinfunction "7_7") (pintype "unspecified"))
      (node (ref "U1") (pin "38") (pinfunction "IO2_38") (pintype "unspecified"))
    )
    (net (code "54") (name "U1_TX") (class "Default")
      (node (ref "CN1") (pin "6") (pinfunction "6_6") (pintype "unspecified"))
      (node (ref "U1") (pin "39") (pinfunction "IO1_39") (pintype "unspecified"))
    )
    (net (code "55") (name "VBUS") (class "Default")
      (node (ref "D4") (pin "2") (pinfunction "A_2") (pintype "unspecified"))
      (node (ref "D7") (pin "2") (pinfunction "2_2") (pintype "unspecified"))
      (node (ref "USB2") (pin "A4") (pinfunction "VBUS_A4") (pintype "unspecified"))
      (node (ref "USB2") (pin "A9") (pinfunction "VBUS_A9") (pintype "unspecified"))
      (node (ref "USB2") (pin "B4") (pinfunction "VBUS_B4") (pintype "unspecified"))
      (node (ref "USB2") (pin "B9") (pinfunction "VBUS_B9") (pintype "unspecified"))
    )
    (net (code "56") (name "VSYNC") (class "Default")
      (node (ref "FPC4") (pin "7") (pinfunction "7_7") (pintype "input"))
      (node (ref "U1") (pin "15") (pinfunction "IO3_15") (pintype "unspecified"))
    )
    (net (code "57") (name "unconnected-(CN1-Pad8)") (class "Default")
      (node (ref "CN1") (pin "8") (pinfunction "8_8") (pintype "unspecified"))
    )
    (net (code "58") (name "unconnected-(CN1-Pad9)") (class "Default")
      (node (ref "CN1") (pin "9") (pinfunction "9_9") (pintype "unspecified"))
    )
    (net (code "59") (name "unconnected-(FPC4-Pad1)") (class "Default")
      (node (ref "FPC4") (pin "1") (pinfunction "1_1") (pintype "input+no_connect"))
    )
    (net (code "60") (name "unconnected-(FPC4-Pad23)") (class "Default")
      (node (ref "FPC4") (pin "23") (pinfunction "23_23") (pintype "input+no_connect"))
    )
    (net (code "61") (name "unconnected-(FPC4-Pad24)") (class "Default")
      (node (ref "FPC4") (pin "24") (pinfunction "24_24") (pintype "input+no_connect"))
    )
    (net (code "62") (name "unconnected-(SW1-Pad2)") (class "Default")
      (node (ref "SW1") (pin "2") (pinfunction "2_2") (pintype "unspecified"))
    )
    (net (code "63") (name "unconnected-(SW1-Pad3)") (class "Default")
      (node (ref "SW1") (pin "3") (pinfunction "3_3") (pintype "unspecified"))
    )
    (net (code "64") (name "unconnected-(SW2-Pad2)") (class "Default")
      (node (ref "SW2") (pin "2") (pinfunction "2_2") (pintype "unspecified"))
    )
    (net (code "65") (name "unconnected-(SW2-Pad3)") (class "Default")
      (node (ref "SW2") (pin "3") (pinfunction "3_3") (pintype "unspecified"))
    )
    (net (code "66") (name "unconnected-(SW3-Pad2)") (class "Default")
      (node (ref "SW3") (pin "2") (pinfunction "2_2") (pintype "unspecified"))
    )
    (net (code "67") (name "unconnected-(SW3-Pad3)") (class "Default")
      (node (ref "SW3") (pin "3") (pinfunction "3_3") (pintype "unspecified"))
    )
    (net (code "68") (name "unconnected-(U2-GPIO0{slash}RI#{slash}RWK#-Pad8)") (class "Default")
      (node (ref "U2") (pin "8") (pinfunction "GPIO0/RI#/RWK#_8") (pintype "unspecified+no_connect"))
    )
    (net (code "69") (name "unconnected-(U2-GPIO1{slash}CD#-Pad7)") (class "Default")
      (node (ref "U2") (pin "7") (pinfunction "GPIO1/CD#_7") (pintype "unspecified+no_connect"))
    )
    (net (code "70") (name "unconnected-(U2-GPIO2{slash}DSR#-Pad6)") (class "Default")
      (node (ref "U2") (pin "6") (pinfunction "GPIO2/DSR#_6") (pintype "unspecified+no_connect"))
    )
    (net (code "71") (name "unconnected-(U2-GPIO3{slash}DTR#-Pad5)") (class "Default")
      (node (ref "U2") (pin "5") (pinfunction "GPIO3/DTR#_5") (pintype "unspecified+no_connect"))
    )
    (net (code "72") (name "unconnected-(U2-GPIO4{slash}CTS#-Pad4)") (class "Default")
      (node (ref "U2") (pin "4") (pinfunction "GPIO4/CTS#_4") (pintype "unspecified+no_connect"))
    )
    (net (code "73") (name "unconnected-(U2-GPIO5{slash}RTS#{slash}RS485-Pad3)") (class "Default")
      (node (ref "U2") (pin "3") (pinfunction "GPIO5/RTS#/RS485_3") (pintype "unspecified+no_connect"))
    )
    (net (code "74") (name "unconnected-(U2-LOWPOWER-Pad2)") (class "Default")
      (node (ref "U2") (pin "2") (pinfunction "LOWPOWER_2") (pintype "unspecified+no_connect"))
    )
    (net (code "75") (name "unconnected-(U2-SCL-Pad12)") (class "Default")
      (node (ref "U2") (pin "12") (pinfunction "SCL_12") (pintype "unspecified+no_connect"))
    )
    (net (code "76") (name "unconnected-(U2-SDA-Pad11)") (class "Default")
      (node (ref "U2") (pin "11") (pinfunction "SDA_11") (pintype "unspecified+no_connect"))
    )
    (net (code "77") (name "unconnected-(U7-NC-Pad4)") (class "Default")
      (node (ref "U7") (pin "4") (pinfunction "NC_4") (pintype "unspecified"))
    )
    (net (code "78") (name "unconnected-(USB1-SBU1-PadA8)") (class "Default")
      (node (ref "USB1") (pin "A8") (pinfunction "SBU1_A8") (pintype "unspecified"))
    )
    (net (code "79") (name "unconnected-(USB1-SBU2-PadB8)") (class "Default")
      (node (ref "USB1") (pin "B8") (pinfunction "SBU2_B8") (pintype "unspecified"))
    )
    (net (code "80") (name "unconnected-(USB1-SH-Pad0)") (class "Default")
      (node (ref "USB1") (pin "0") (pinfunction "SH_0") (pintype "unspecified"))
    )
    (net (code "81") (name "unconnected-(USB1-SH-Pad1)") (class "Default")
      (node (ref "USB1") (pin "1") (pinfunction "SH_1") (pintype "unspecified"))
    )
    (net (code "82") (name "unconnected-(USB1-SH-Pad2)") (class "Default")
      (node (ref "USB1") (pin "2") (pinfunction "SH_2") (pintype "unspecified"))
    )
    (net (code "83") (name "unconnected-(USB1-SH-Pad3)") (class "Default")
      (node (ref "USB1") (pin "3") (pinfunction "SH_3") (pintype "unspecified"))
    )
    (net (code "84") (name "unconnected-(USB2-SBU1-PadA8)") (class "Default")
      (node (ref "USB2") (pin "A8") (pinfunction "SBU1_A8") (pintype "unspecified"))
    )
    (net (code "85") (name "unconnected-(USB2-SBU2-PadB8)") (class "Default")
      (node (ref "USB2") (pin "B8") (pinfunction "SBU2_B8") (pintype "unspecified"))
    )
    (net (code "86") (name "unconnected-(USB2-SH-Pad0)") (class "Default")
      (node (ref "USB2") (pin "0") (pinfunction "SH_0") (pintype "unspecified"))
    )
    (net (code "87") (name "unconnected-(USB2-SH-Pad1)") (class "Default")
      (node (ref "USB2") (pin "1") (pinfunction "SH_1") (pintype "unspecified"))
    )
    (net (code "88") (name "unconnected-(USB2-SH-Pad2)") (class "Default")
      (node (ref "USB2") (pin "2") (pinfunction "SH_2") (pintype "unspecified"))
    )
    (net (code "89") (name "unconnected-(USB2-SH-Pad3)") (class "Default")
      (node (ref "USB2") (pin "3") (pinfunction "SH_3") (pintype "unspecified"))
    )
  )
)
